# MRDT0003A2.net
KiCad netlist of a schematic drawn in EAGLE
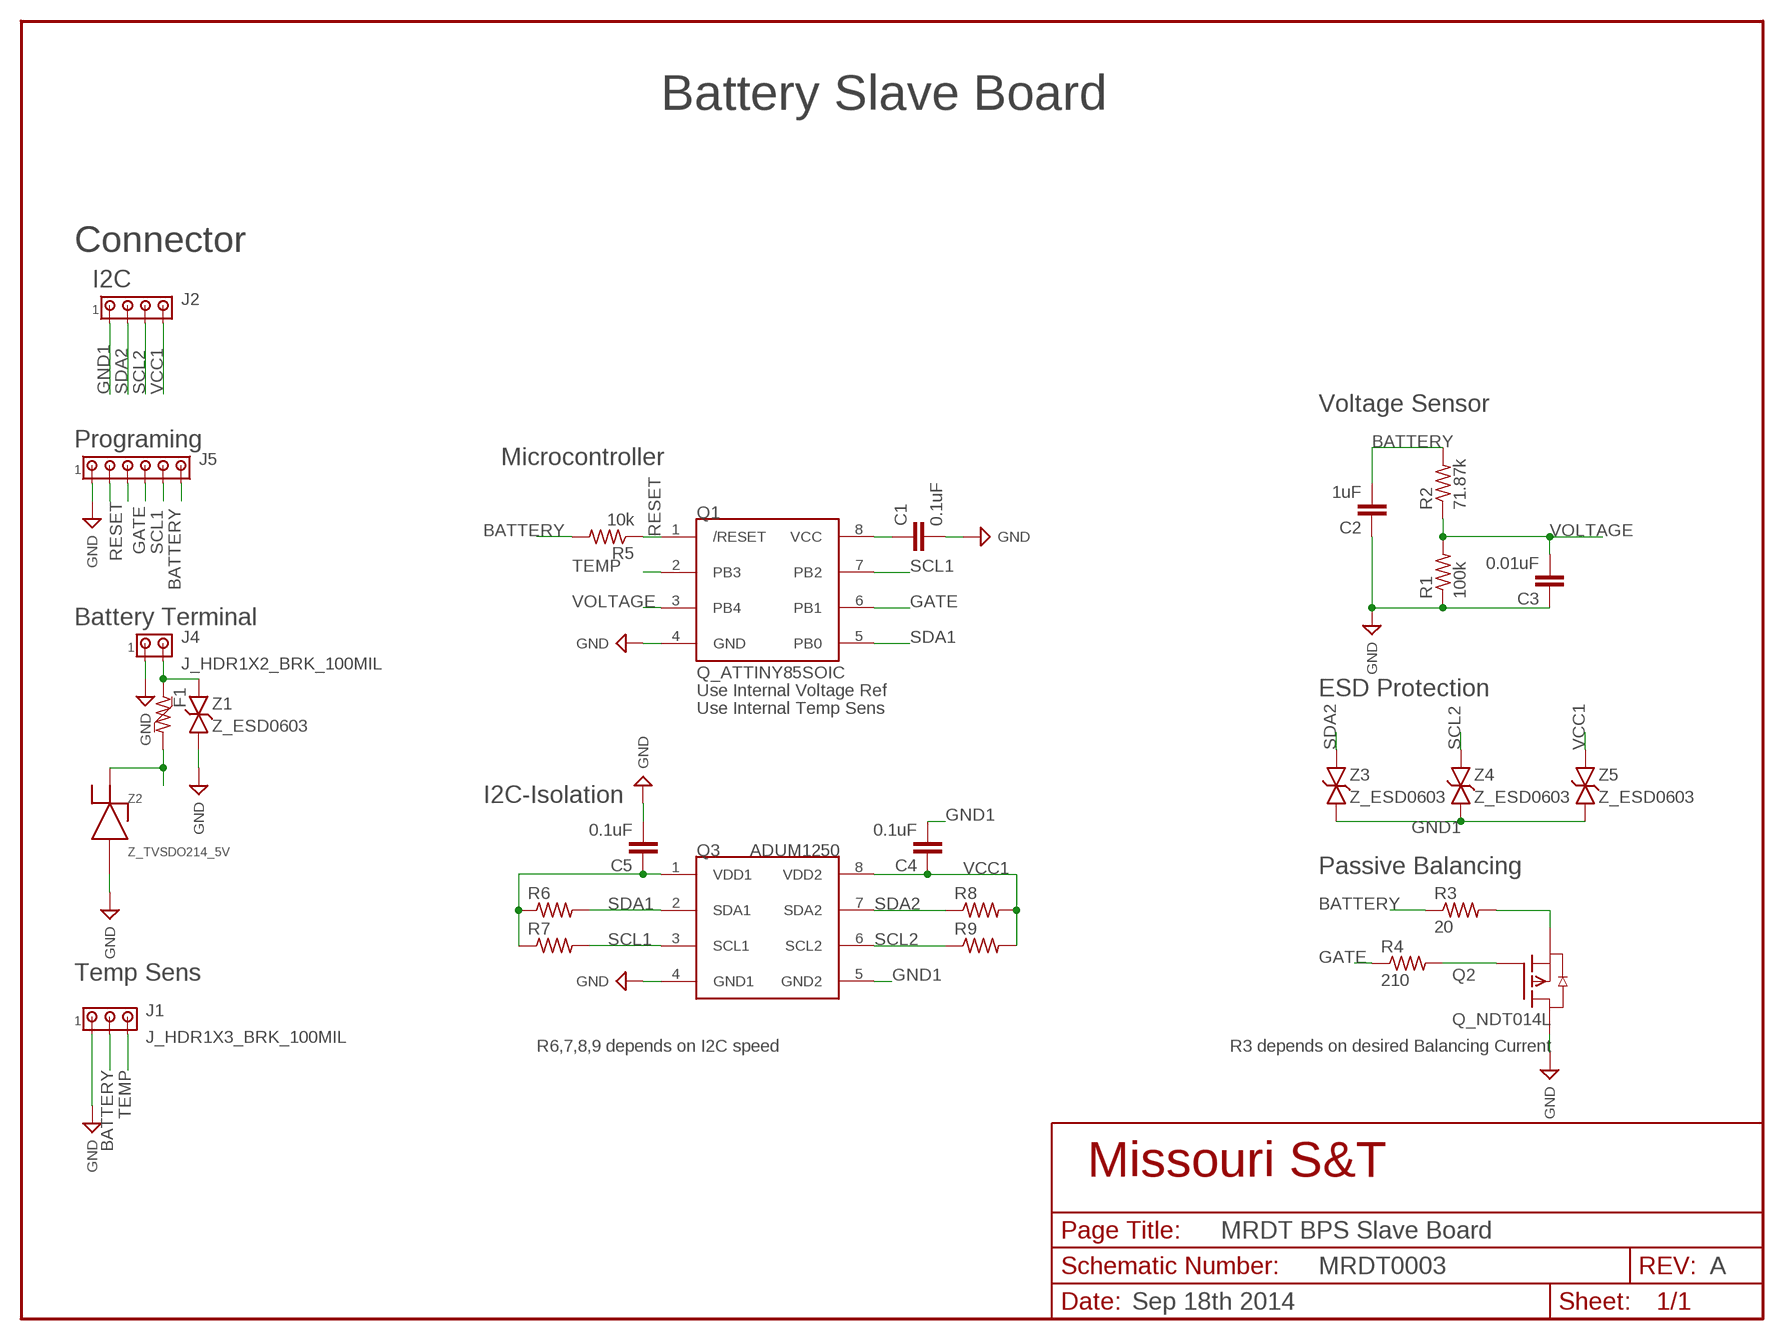
[diagram p0: schematic, sheet 1]

(export (version "E")
  (design (tool "Eeschema 10.0.6"))
  (components
    (comp (ref "C1")
      (value "0.1uF")
      (footprint "eagle-import:C_0805")
      (libsource (lib "eagle-import") (part "C_CAP_0805"))
    )
    (comp (ref "C2")
      (value "1uF")
      (footprint "eagle-import:C_0805")
      (libsource (lib "eagle-import") (part "C_CAP_0805"))
    )
    (comp (ref "C3")
      (value "0.01uF")
      (footprint "eagle-import:C_0805")
      (libsource (lib "eagle-import") (part "C_CAP_0805"))
    )
    (comp (ref "C4")
      (value "0.1uF")
      (footprint "eagle-import:C_0805")
      (libsource (lib "eagle-import") (part "C_CAP_0805"))
    )
    (comp (ref "C5")
      (value "0.1uF")
      (footprint "eagle-import:C_0805")
      (libsource (lib "eagle-import") (part "C_CAP_0805"))
    )
    (comp (ref "F1")
      (value "R_RES_1210")
      (footprint "eagle-import:R_1210")
      (libsource (lib "eagle-import") (part "R_RES_1210"))
    )
    (comp (ref "J1")
      (value "J_HDR1X3_BRK_100MIL")
      (footprint "eagle-import:J_BRK1X3_100MIL")
      (libsource (lib "eagle-import") (part "J_HDR1X3_BRK_100MIL"))
    )
    (comp (ref "J2")
      (value "J_HDR1X4_BRK_100MIL")
      (footprint "eagle-import:J_BRK1X4_100MIL")
      (libsource (lib "eagle-import") (part "J_HDR1X4_BRK_100MIL"))
    )
    (comp (ref "J4")
      (value "J_HDR1X2_BRK_100MIL")
      (footprint "eagle-import:J_BRK1X2_100MIL")
      (libsource (lib "eagle-import") (part "J_HDR1X2_BRK_100MIL"))
    )
    (comp (ref "J5")
      (value "J_HDR1X6_BRK_100MIL")
      (footprint "eagle-import:J_BRK1X6_100MIL")
      (libsource (lib "eagle-import") (part "J_HDR1X6_BRK_100MIL"))
    )
    (comp (ref "Q1")
      (value "Q_ATTINY85SOIC")
      (footprint "eagle-import:SOIC8")
      (libsource (lib "eagle-import") (part "Q_ATTINY85SOIC"))
    )
    (comp (ref "Q2")
      (value "Q_NDT014L")
      (footprint "eagle-import:SOT-223")
      (libsource (lib "eagle-import") (part "Q_BSP315P"))
    )
    (comp (ref "Q3")
      (value "ADUM1250")
      (footprint "eagle-import:SOIC8")
      (libsource (lib "eagle-import") (part "Q_ADUM1250SOIC"))
    )
    (comp (ref "R1")
      (value "100k")
      (footprint "eagle-import:R_0805")
      (libsource (lib "eagle-import") (part "R_RES_0805"))
    )
    (comp (ref "R2")
      (value "71.87k")
      (footprint "eagle-import:R_0805")
      (libsource (lib "eagle-import") (part "R_RES_0805"))
    )
    (comp (ref "R3")
      (value "20")
      (footprint "eagle-import:R_2010")
      (libsource (lib "eagle-import") (part "R_RES_2010"))
    )
    (comp (ref "R4")
      (value "210")
      (footprint "eagle-import:R_0805")
      (libsource (lib "eagle-import") (part "R_RES_0805"))
    )
    (comp (ref "R5")
      (value "10k")
      (footprint "eagle-import:R_0805")
      (libsource (lib "eagle-import") (part "R_RES_0805"))
    )
    (comp (ref "R6")
      (value "R_RES_0805")
      (footprint "eagle-import:R_0805")
      (libsource (lib "eagle-import") (part "R_RES_0805"))
    )
    (comp (ref "R7")
      (value "R_RES_1206")
      (footprint "eagle-import:R_1206")
      (libsource (lib "eagle-import") (part "R_RES_1206"))
    )
    (comp (ref "R8")
      (value "R_RES_1206")
      (footprint "eagle-import:R_1206")
      (libsource (lib "eagle-import") (part "R_RES_1206"))
    )
    (comp (ref "R9")
      (value "R_RES_1206")
      (footprint "eagle-import:R_1206")
      (libsource (lib "eagle-import") (part "R_RES_1206"))
    )
    (comp (ref "Z1")
      (value "Z_ESD0603")
      (footprint "eagle-import:0603")
      (libsource (lib "eagle-import") (part "Z_ESD0603"))
    )
    (comp (ref "Z2")
      (value "Z_TVSDO214_5V")
      (footprint "eagle-import:DO-214AC")
      (libsource (lib "eagle-import") (part "Z_TVSDO214"))
    )
    (comp (ref "Z3")
      (value "Z_ESD0603")
      (footprint "eagle-import:0603")
      (libsource (lib "eagle-import") (part "Z_ESD0603"))
    )
    (comp (ref "Z4")
      (value "Z_ESD0603")
      (footprint "eagle-import:0603")
      (libsource (lib "eagle-import") (part "Z_ESD0603"))
    )
    (comp (ref "Z5")
      (value "Z_ESD0603")
      (footprint "eagle-import:0603")
      (libsource (lib "eagle-import") (part "Z_ESD0603"))
    )
  )
  (nets
    (net (code "1") (name "/BATTERY") (class "Default")
      (node (ref "C1") (pin "1") (pinfunction "1_1") (pintype "passive"))
      (node (ref "C2") (pin "2") (pinfunction "2_2") (pintype "passive"))
      (node (ref "C5") (pin "1") (pinfunction "1_1") (pintype "passive"))
      (node (ref "F1") (pin "2") (pinfunction "2_2") (pintype "passive"))
      (node (ref "J1") (pin "2") (pinfunction "2_2") (pintype "passive"))
      (node (ref "J5") (pin "6") (pinfunction "6_6") (pintype "passive"))
      (node (ref "Q1") (pin "8") (pinfunction "VCC_8") (pintype "bidirectional"))
      (node (ref "Q3") (pin "1") (pinfunction "VDD1_1") (pintype "bidirectional"))
      (node (ref "R2") (pin "2") (pinfunction "2_2") (pintype "passive"))
      (node (ref "R3") (pin "1") (pinfunction "1_1") (pintype "passive"))
      (node (ref "R5") (pin "2") (pinfunction "2_2") (pintype "passive"))
      (node (ref "R6") (pin "1") (pinfunction "1_1") (pintype "passive"))
      (node (ref "R7") (pin "1") (pinfunction "1_1") (pintype "passive"))
      (node (ref "Z2") (pin "C") (pinfunction "C_C") (pintype "bidirectional"))
    )
    (net (code "2") (name "/GATE") (class "Default")
      (node (ref "J5") (pin "3") (pinfunction "3_3") (pintype "passive"))
      (node (ref "Q1") (pin "6") (pinfunction "PB1_6") (pintype "bidirectional"))
      (node (ref "R4") (pin "1") (pinfunction "1_1") (pintype "passive"))
    )
    (net (code "3") (name "/GND1") (class "Default")
      (node (ref "C4") (pin "2") (pinfunction "2_2") (pintype "passive"))
      (node (ref "J2") (pin "1") (pinfunction "1_1") (pintype "passive"))
      (node (ref "Q3") (pin "5") (pinfunction "GND2_5") (pintype "bidirectional"))
      (node (ref "Z3") (pin "1") (pinfunction "P$1_1") (pintype "bidirectional"))
      (node (ref "Z4") (pin "1") (pinfunction "P$1_1") (pintype "bidirectional"))
      (node (ref "Z5") (pin "1") (pinfunction "P$1_1") (pintype "bidirectional"))
    )
    (net (code "4") (name "/RESET") (class "Default")
      (node (ref "J5") (pin "2") (pinfunction "2_2") (pintype "passive"))
      (node (ref "Q1") (pin "1") (pinfunction "/RESET_1") (pintype "bidirectional"))
      (node (ref "R5") (pin "1") (pinfunction "1_1") (pintype "passive"))
    )
    (net (code "5") (name "/SCL1") (class "Default")
      (node (ref "J5") (pin "4") (pinfunction "4_4") (pintype "passive"))
      (node (ref "Q1") (pin "7") (pinfunction "PB2_7") (pintype "bidirectional"))
      (node (ref "Q3") (pin "3") (pinfunction "SCL1_3") (pintype "bidirectional"))
      (node (ref "R7") (pin "2") (pinfunction "2_2") (pintype "passive"))
    )
    (net (code "6") (name "/SCL2") (class "Default")
      (node (ref "J2") (pin "3") (pinfunction "3_3") (pintype "passive"))
      (node (ref "Q3") (pin "6") (pinfunction "SCL2_6") (pintype "bidirectional"))
      (node (ref "R9") (pin "1") (pinfunction "1_1") (pintype "passive"))
      (node (ref "Z4") (pin "2") (pinfunction "P$2_2") (pintype "bidirectional"))
    )
    (net (code "7") (name "/SDA1") (class "Default")
      (node (ref "J5") (pin "5") (pinfunction "5_5") (pintype "passive"))
      (node (ref "Q1") (pin "5") (pinfunction "PB0_5") (pintype "bidirectional"))
      (node (ref "Q3") (pin "2") (pinfunction "SDA1_2") (pintype "bidirectional"))
      (node (ref "R6") (pin "2") (pinfunction "2_2") (pintype "passive"))
    )
    (net (code "8") (name "/SDA2") (class "Default")
      (node (ref "J2") (pin "2") (pinfunction "2_2") (pintype "passive"))
      (node (ref "Q3") (pin "7") (pinfunction "SDA2_7") (pintype "bidirectional"))
      (node (ref "R8") (pin "1") (pinfunction "1_1") (pintype "passive"))
      (node (ref "Z3") (pin "2") (pinfunction "P$2_2") (pintype "bidirectional"))
    )
    (net (code "9") (name "/TEMP") (class "Default")
      (node (ref "J1") (pin "3") (pinfunction "3_3") (pintype "passive"))
      (node (ref "Q1") (pin "2") (pinfunction "PB3_2") (pintype "bidirectional"))
    )
    (net (code "10") (name "/VCC1") (class "Default")
      (node (ref "C4") (pin "1") (pinfunction "1_1") (pintype "passive"))
      (node (ref "J2") (pin "4") (pinfunction "4_4") (pintype "passive"))
      (node (ref "Q3") (pin "8") (pinfunction "VDD2_8") (pintype "bidirectional"))
      (node (ref "R8") (pin "2") (pinfunction "2_2") (pintype "passive"))
      (node (ref "R9") (pin "2") (pinfunction "2_2") (pintype "passive"))
      (node (ref "Z5") (pin "2") (pinfunction "P$2_2") (pintype "bidirectional"))
    )
    (net (code "11") (name "/VOLTAGE") (class "Default")
      (node (ref "C3") (pin "2") (pinfunction "2_2") (pintype "passive"))
      (node (ref "Q1") (pin "3") (pinfunction "PB4_3") (pintype "bidirectional"))
      (node (ref "R1") (pin "2") (pinfunction "2_2") (pintype "passive"))
      (node (ref "R2") (pin "1") (pinfunction "1_1") (pintype "passive"))
    )
    (net (code "12") (name "Net-(Q2-G)") (class "Default")
      (node (ref "Q2") (pin "1") (pinfunction "G_1") (pintype "passive"))
      (node (ref "R4") (pin "2") (pinfunction "2_2") (pintype "passive"))
    )
    (net (code "13") (name "Net-(Q2-S)") (class "Default")
      (node (ref "Q2") (pin "3") (pinfunction "S_3") (pintype "passive"))
      (node (ref "R3") (pin "2") (pinfunction "2_2") (pintype "passive"))
    )
    (net (code "14") (name "Net-(Z1-P$2)") (class "Default")
      (node (ref "F1") (pin "1") (pinfunction "1_1") (pintype "passive"))
      (node (ref "J4") (pin "2") (pinfunction "2_2") (pintype "passive"))
      (node (ref "Z1") (pin "2") (pinfunction "P$2_2") (pintype "bidirectional"))
    )
    (net (code "15") (name "SUP_GND") (class "Default")
      (node (ref "C1") (pin "2") (pinfunction "2_2") (pintype "passive"))
      (node (ref "C2") (pin "1") (pinfunction "1_1") (pintype "passive"))
      (node (ref "C3") (pin "1") (pinfunction "1_1") (pintype "passive"))
      (node (ref "C5") (pin "2") (pinfunction "2_2") (pintype "passive"))
      (node (ref "J1") (pin "1") (pinfunction "1_1") (pintype "passive"))
      (node (ref "J4") (pin "1") (pinfunction "1_1") (pintype "passive"))
      (node (ref "J5") (pin "1") (pinfunction "1_1") (pintype "passive"))
      (node (ref "Q1") (pin "4") (pinfunction "GND_4") (pintype "bidirectional"))
      (node (ref "Q2") (pin "2") (pinfunction "D_2") (pintype "passive"))
      (node (ref "Q3") (pin "4") (pinfunction "GND1_4") (pintype "bidirectional"))
      (node (ref "R1") (pin "1") (pinfunction "1_1") (pintype "passive"))
      (node (ref "Z1") (pin "1") (pinfunction "P$1_1") (pintype "bidirectional"))
      (node (ref "Z2") (pin "A") (pinfunction "A_A") (pintype "bidirectional"))
    )
  )
)
